# Main.net
KiCad netlist of a schematic drawn in Altium Designer
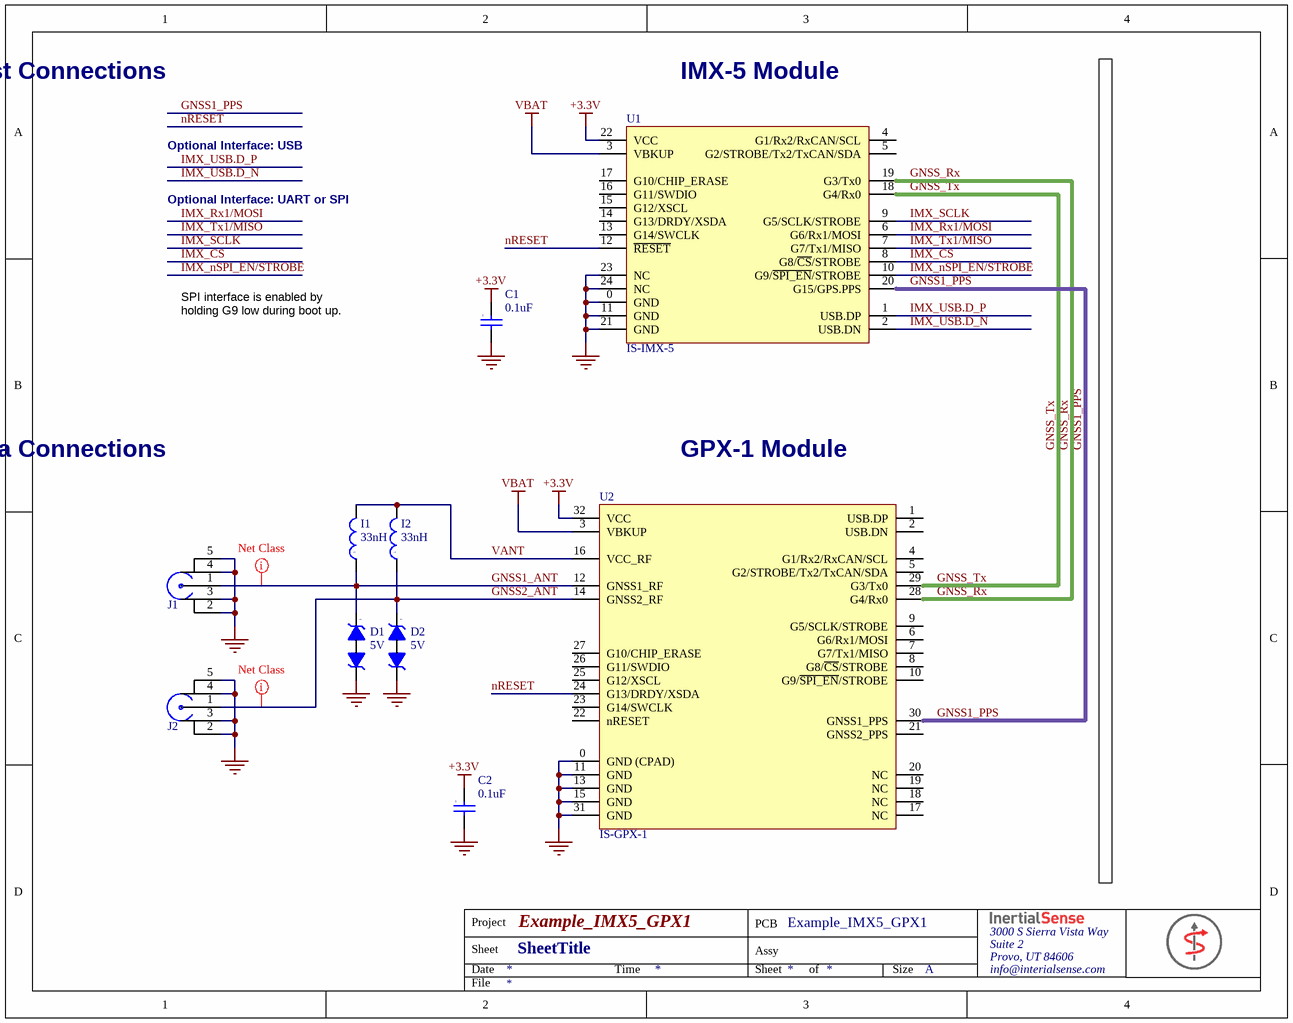
[diagram p0: Main.SchDoc]

(export (version "E")
  (design (tool "Eeschema 10.0.6"))
  (components
    (comp (ref "C1")
      (value "0.1uF")
      (footprint "0402")
      (description "Capacitor")
      (fields (field (name "Comment") "Cap") (field (name "PUBLISHER") "Altium Limited"))
      (libsource (lib "General") (part "Cap"))
    )
    (comp (ref "C2")
      (value "0.1uF")
      (footprint "0402")
      (description "Capacitor")
      (fields (field (name "Comment") "Cap") (field (name "PUBLISHER") "Altium Limited"))
      (libsource (lib "General") (part "Cap"))
    )
    (comp (ref "D1")
      (value "Diode - Bidirectional Zener")
      (footprint "D0201")
      (description "TVS DIODE 12VC 6A IPP 0201")
      (fields
        (field (name "MANUFACTURER") "AVX Corporation")
        (field (name "MANUFACTURER PART NUMBER") "GG020105100N2P")
        (field (name "VOLTAGE - REVERSE STANDOFF (TYP)") "5V")
      )
      (libsource (lib "General") (part "Diode - Bidirectional Zener"))
    )
    (comp (ref "D2")
      (value "Diode - Bidirectional Zener")
      (footprint "D0201")
      (description "TVS DIODE 12VC 6A IPP 0201")
      (fields
        (field (name "MANUFACTURER") "AVX Corporation")
        (field (name "MANUFACTURER PART NUMBER") "GG020105100N2P")
        (field (name "VOLTAGE - REVERSE STANDOFF (TYP)") "5V")
      )
      (libsource (lib "General") (part "Diode - Bidirectional Zener"))
    )
    (comp (ref "I1")
      (value "33nH")
      (footprint "0201")
      (description "Inductor")
      (libsource (lib "General") (part "Inductor"))
    )
    (comp (ref "I2")
      (value "33nH")
      (footprint "0201")
      (description "Inductor")
      (libsource (lib "General") (part "Inductor"))
    )
    (comp (ref "J1")
      (value "RF - GND x 4")
      (footprint "RF SMA End Launch 2")
      (description "CONN SMA RCPT STR 50OHM EDGE MNT")
      (fields (field (name "MANUFACTURER") "Molex") (field (name "MANUFACTURER PART NUMBER") "0732511150"))
      (libsource (lib "Connectors") (part "RF - GND x 4"))
    )
    (comp (ref "J2")
      (value "RF - GND x 4")
      (footprint "RF SMA End Launch 2")
      (description "CONN SMA RCPT STR 50OHM EDGE MNT")
      (fields (field (name "MANUFACTURER") "Molex") (field (name "MANUFACTURER PART NUMBER") "0732511150"))
      (libsource (lib "Connectors") (part "RF - GND x 4"))
    )
    (comp (ref "U1")
      (value "IMX")
      (footprint "IS-IMX-5.0")
      (description "Inertial Sense IMX")
      (fields
        (field (name "MANUFACTURER") "Inertial Sense")
        (field (name "MANUFACTURER PART NUMBER") "IS-IMX-5")
      )
      (libsource (lib "IS-IMX-5") (part "IS-IMX-5.0"))
    )
    (comp (ref "U2")
      (value "GPX")
      (footprint "IS-GPX-1.0")
      (description "Inertial Sense GPX")
      (fields
        (field (name "MANUFACTURER") "Inertial Sense")
        (field (name "MANUFACTURER PART NUMBER") "IS-GPX-1")
      )
      (libsource (lib "IS-GPX-1") (part "IS-GPX-1.0"))
    )
  )
  (nets
    (net (code "1") (name "+3.3V") (class "Default")
      (node (ref "C1") (pin "1") (pinfunction "1_1") (pintype "passive"))
      (node (ref "C2") (pin "1") (pinfunction "1_1") (pintype "passive"))
      (node (ref "U1") (pin "22") (pinfunction "VCC_22") (pintype "power_in"))
      (node (ref "U2") (pin "32") (pinfunction "VCC_32") (pintype "power_in"))
    )
    (net (code "2") (name "/GNSS1_ANT") (class "Default")
      (node (ref "D1") (pin "1") (pinfunction "1_1") (pintype "passive"))
      (node (ref "I1") (pin "1") (pinfunction "1_1") (pintype "passive"))
      (node (ref "J1") (pin "1") (pinfunction "1_1") (pintype "passive"))
      (node (ref "U2") (pin "12") (pinfunction "GNSS1_RF_12") (pintype "passive"))
    )
    (net (code "3") (name "/GNSS1_PPS") (class "Default")
      (node (ref "U1") (pin "20") (pinfunction "G15/GPS.PPS_20") (pintype "passive"))
      (node (ref "U2") (pin "30") (pinfunction "GNSS1_PPS_30") (pintype "passive"))
    )
    (net (code "4") (name "/GNSS2_ANT") (class "Default")
      (node (ref "D2") (pin "1") (pinfunction "1_1") (pintype "passive"))
      (node (ref "I2") (pin "1") (pinfunction "1_1") (pintype "passive"))
      (node (ref "J2") (pin "1") (pinfunction "1_1") (pintype "passive"))
      (node (ref "U2") (pin "14") (pinfunction "GNSS2_RF_14") (pintype "passive"))
    )
    (net (code "5") (name "/GNSS_Rx") (class "Default")
      (node (ref "U1") (pin "19") (pinfunction "G3/Tx0_19") (pintype "passive"))
      (node (ref "U2") (pin "28") (pinfunction "G4/Rx0_28") (pintype "passive"))
    )
    (net (code "6") (name "/GNSS_Tx") (class "Default")
      (node (ref "U1") (pin "18") (pinfunction "G4/Rx0_18") (pintype "passive"))
      (node (ref "U2") (pin "29") (pinfunction "G3/Tx0_29") (pintype "passive"))
    )
    (net (code "7") (name "/IMX_Rx1{slash}MOSI") (class "Default")
      (node (ref "U1") (pin "6") (pinfunction "G6/Rx1/MOSI_6") (pintype "passive"))
    )
    (net (code "8") (name "/IMX_SCLK") (class "Default")
      (node (ref "U1") (pin "9") (pinfunction "G5/SCLK/STROBE_9") (pintype "passive"))
    )
    (net (code "9") (name "/IMX_Tx1{slash}MISO") (class "Default")
      (node (ref "U1") (pin "7") (pinfunction "G7/Tx1/MISO_7") (pintype "passive"))
    )
    (net (code "10") (name "/IMX_USB.D_N") (class "Default")
      (node (ref "U1") (pin "2") (pinfunction "USB.DN_2") (pintype "passive"))
    )
    (net (code "11") (name "/IMX_USB.D_P") (class "Default")
      (node (ref "U1") (pin "1") (pinfunction "USB.DP_1") (pintype "passive"))
    )
    (net (code "12") (name "/IMX_nSPI_EN{slash}STROBE") (class "Default")
      (node (ref "U1") (pin "10") (pinfunction "G9/~{SPI_EN}/STROBE_10") (pintype "passive"))
    )
    (net (code "13") (name "/IMX_~{CS}") (class "Default")
      (node (ref "U1") (pin "8") (pinfunction "G8/~{CS}/STROBE_8") (pintype "passive"))
    )
    (net (code "14") (name "/VANT") (class "Default")
      (node (ref "I1") (pin "2") (pinfunction "2_2") (pintype "passive"))
      (node (ref "I2") (pin "2") (pinfunction "2_2") (pintype "passive"))
      (node (ref "U2") (pin "16") (pinfunction "VCC_RF_16") (pintype "power_in"))
    )
    (net (code "15") (name "/nRESET") (class "Default")
      (node (ref "U1") (pin "12") (pinfunction "~{RESET}_12") (pintype "passive"))
      (node (ref "U2") (pin "24") (pinfunction "G13/DRDY/XSDA_24") (pintype "passive"))
    )
    (net (code "16") (name "GND") (class "Default")
      (node (ref "C1") (pin "2") (pinfunction "2_2") (pintype "passive"))
      (node (ref "C2") (pin "2") (pinfunction "2_2") (pintype "passive"))
      (node (ref "D1") (pin "2") (pinfunction "2_2") (pintype "passive"))
      (node (ref "D2") (pin "2") (pinfunction "2_2") (pintype "passive"))
      (node (ref "J1") (pin "2") (pinfunction "2_2") (pintype "passive"))
      (node (ref "J1") (pin "3") (pinfunction "3_3") (pintype "passive"))
      (node (ref "J1") (pin "4") (pinfunction "4_4") (pintype "passive"))
      (node (ref "J1") (pin "5") (pinfunction "5_5") (pintype "passive"))
      (node (ref "J2") (pin "2") (pinfunction "2_2") (pintype "passive"))
      (node (ref "J2") (pin "3") (pinfunction "3_3") (pintype "passive"))
      (node (ref "J2") (pin "4") (pinfunction "4_4") (pintype "passive"))
      (node (ref "J2") (pin "5") (pinfunction "5_5") (pintype "passive"))
      (node (ref "U1") (pin "0") (pinfunction "GND_0") (pintype "power_in"))
      (node (ref "U1") (pin "11") (pinfunction "GND_11") (pintype "power_in"))
      (node (ref "U1") (pin "21") (pinfunction "GND_21") (pintype "power_in"))
      (node (ref "U1") (pin "23") (pinfunction "NC_23") (pintype "power_in"))
      (node (ref "U1") (pin "24") (pinfunction "NC_24") (pintype "power_in"))
      (node (ref "U2") (pin "0") (pinfunction "GND_(CPAD)_0") (pintype "power_in"))
      (node (ref "U2") (pin "11") (pinfunction "GND_11") (pintype "power_in"))
      (node (ref "U2") (pin "13") (pinfunction "GND_13") (pintype "power_in"))
      (node (ref "U2") (pin "15") (pinfunction "GND_15") (pintype "power_in"))
      (node (ref "U2") (pin "31") (pinfunction "GND_31") (pintype "power_in"))
    )
    (net (code "17") (name "VBAT") (class "Default")
      (node (ref "U1") (pin "3") (pinfunction "VBKUP_3") (pintype "passive"))
      (node (ref "U2") (pin "3") (pinfunction "VBKUP_3") (pintype "passive"))
    )
    (net (code "18") (name "unconnected-(U1-G1{slash}Rx2{slash}RxCAN{slash}SCL-Pad4)") (class "Default")
      (node (ref "U1") (pin "4") (pinfunction "G1/Rx2/RxCAN/SCL_4") (pintype "passive"))
    )
    (net (code "19") (name "unconnected-(U1-G2{slash}STROBE{slash}Tx2{slash}TxCAN{slash}SDA-Pad5)") (class "Default")
      (node (ref "U1") (pin "5") (pinfunction "G2/STROBE/Tx2/TxCAN/SDA_5") (pintype "passive"))
    )
    (net (code "20") (name "unconnected-(U1-G10{slash}CHIP_ERASE-Pad17)") (class "Default")
      (node (ref "U1") (pin "17") (pinfunction "G10/CHIP_ERASE_17") (pintype "passive"))
    )
    (net (code "21") (name "unconnected-(U1-G11{slash}SWDIO-Pad16)") (class "Default")
      (node (ref "U1") (pin "16") (pinfunction "G11/SWDIO_16") (pintype "passive"))
    )
    (net (code "22") (name "unconnected-(U1-G12{slash}XSCL-Pad15)") (class "Default")
      (node (ref "U1") (pin "15") (pinfunction "G12/XSCL_15") (pintype "passive"))
    )
    (net (code "23") (name "unconnected-(U1-G13{slash}DRDY{slash}XSDA-Pad14)") (class "Default")
      (node (ref "U1") (pin "14") (pinfunction "G13/DRDY/XSDA_14") (pintype "passive"))
    )
    (net (code "24") (name "unconnected-(U1-G14{slash}SWCLK-Pad13)") (class "Default")
      (node (ref "U1") (pin "13") (pinfunction "G14/SWCLK_13") (pintype "passive"))
    )
    (net (code "25") (name "unconnected-(U2-G1{slash}Rx2{slash}RxCAN{slash}SCL-Pad4)") (class "Default")
      (node (ref "U2") (pin "4") (pinfunction "G1/Rx2/RxCAN/SCL_4") (pintype "passive"))
    )
    (net (code "26") (name "unconnected-(U2-G2{slash}STROBE{slash}Tx2{slash}TxCAN{slash}SDA-Pad5)") (class "Default")
      (node (ref "U2") (pin "5") (pinfunction "G2/STROBE/Tx2/TxCAN/SDA_5") (pintype "passive"))
    )
    (net (code "27") (name "unconnected-(U2-G5{slash}SCLK{slash}STROBE-Pad9)") (class "Default")
      (node (ref "U2") (pin "9") (pinfunction "G5/SCLK/STROBE_9") (pintype "passive"))
    )
    (net (code "28") (name "unconnected-(U2-G6{slash}Rx1{slash}MOSI-Pad6)") (class "Default")
      (node (ref "U2") (pin "6") (pinfunction "G6/Rx1/MOSI_6") (pintype "passive"))
    )
    (net (code "29") (name "unconnected-(U2-G7{slash}Tx1{slash}MISO-Pad7)") (class "Default")
      (node (ref "U2") (pin "7") (pinfunction "G7/Tx1/MISO_7") (pintype "passive"))
    )
    (net (code "30") (name "unconnected-(U2-G8{slash}~{CS}{slash}STROBE-Pad8)") (class "Default")
      (node (ref "U2") (pin "8") (pinfunction "G8/~{CS}/STROBE_8") (pintype "passive"))
    )
    (net (code "31") (name "unconnected-(U2-G9{slash}~{SPI_EN}{slash}STROBE-Pad10)") (class "Default")
      (node (ref "U2") (pin "10") (pinfunction "G9/~{SPI_EN}/STROBE_10") (pintype "passive"))
    )
    (net (code "32") (name "unconnected-(U2-G10{slash}CHIP_ERASE-Pad27)") (class "Default")
      (node (ref "U2") (pin "27") (pinfunction "G10/CHIP_ERASE_27") (pintype "passive"))
    )
    (net (code "33") (name "unconnected-(U2-G11{slash}SWDIO-Pad26)") (class "Default")
      (node (ref "U2") (pin "26") (pinfunction "G11/SWDIO_26") (pintype "passive"))
    )
    (net (code "34") (name "unconnected-(U2-G12{slash}XSCL-Pad25)") (class "Default")
      (node (ref "U2") (pin "25") (pinfunction "G12/XSCL_25") (pintype "passive"))
    )
    (net (code "35") (name "unconnected-(U2-G14{slash}SWCLK-Pad23)") (class "Default")
      (node (ref "U2") (pin "23") (pinfunction "G14/SWCLK_23") (pintype "passive"))
    )
    (net (code "36") (name "unconnected-(U2-GNSS2_PPS-Pad21)") (class "Default")
      (node (ref "U2") (pin "21") (pinfunction "GNSS2_PPS_21") (pintype "passive"))
    )
    (net (code "37") (name "unconnected-(U2-NC-Pad17)") (class "Default")
      (node (ref "U2") (pin "17") (pinfunction "NC_17") (pintype "passive"))
    )
    (net (code "38") (name "unconnected-(U2-NC-Pad18)") (class "Default")
      (node (ref "U2") (pin "18") (pinfunction "NC_18") (pintype "passive"))
    )
    (net (code "39") (name "unconnected-(U2-NC-Pad19)") (class "Default")
      (node (ref "U2") (pin "19") (pinfunction "NC_19") (pintype "passive"))
    )
    (net (code "40") (name "unconnected-(U2-NC-Pad20)") (class "Default")
      (node (ref "U2") (pin "20") (pinfunction "NC_20") (pintype "passive"))
    )
    (net (code "41") (name "unconnected-(U2-USB.DN-Pad2)") (class "Default")
      (node (ref "U2") (pin "2") (pinfunction "USB.DN_2") (pintype "passive"))
    )
    (net (code "42") (name "unconnected-(U2-USB.DP-Pad1)") (class "Default")
      (node (ref "U2") (pin "1") (pinfunction "USB.DP_1") (pintype "passive"))
    )
    (net (code "43") (name "unconnected-(U2-nRESET-Pad22)") (class "Default")
      (node (ref "U2") (pin "22") (pinfunction "nRESET_22") (pintype "passive"))
    )
  )
)
